# pi_3_hat_V3.net
KiCad netlist of a schematic drawn in EAGLE
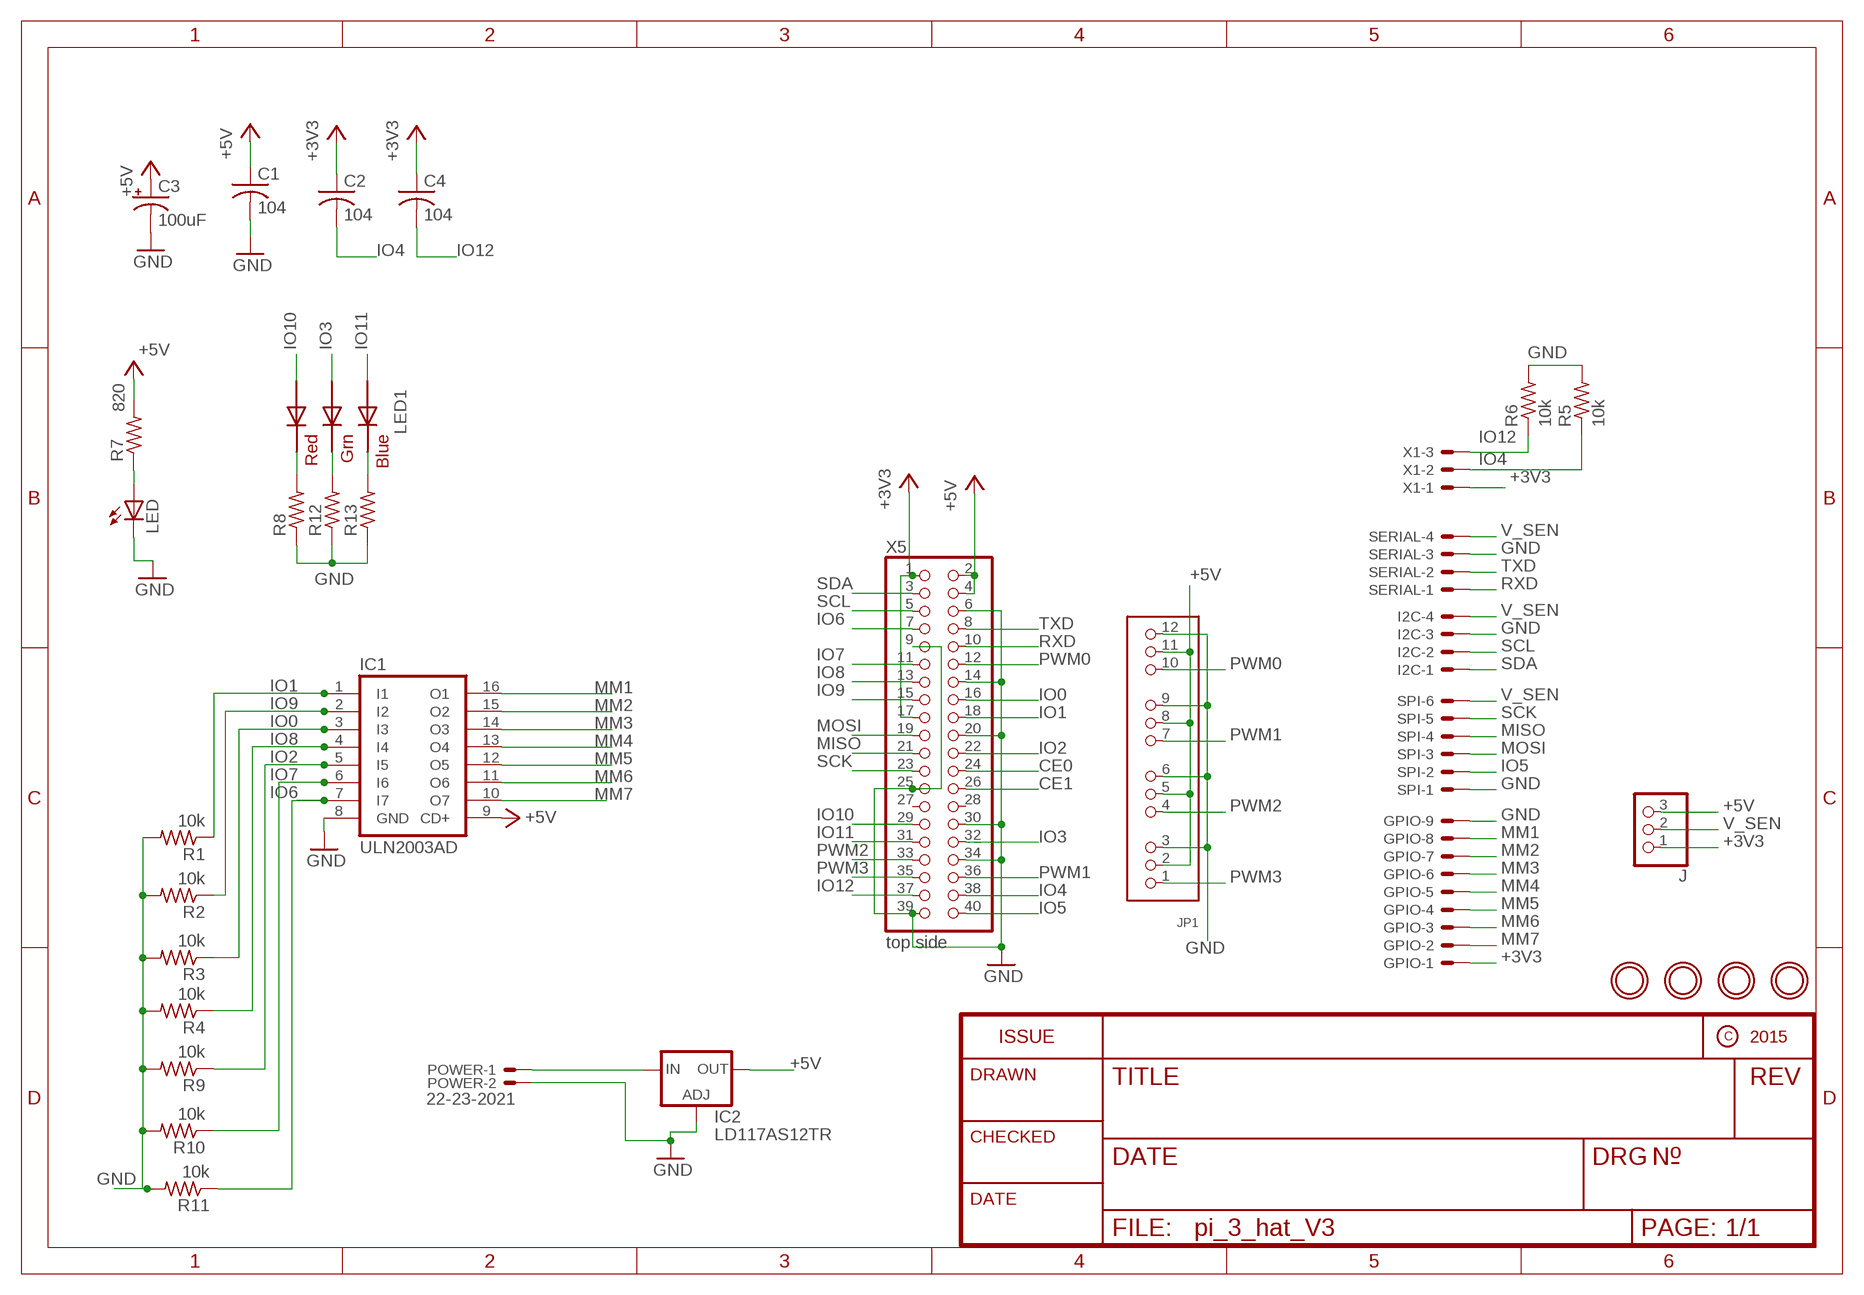
[diagram p0: schematic, sheet 1]

(export (version "E")
  (design (tool "Eeschema 10.0.6"))
  (components
    (comp (ref "C1")
      (value "104")
      (footprint "eagle-import:C1206")
      (libsource (lib "eagle-import") (part "C-USC1206"))
    )
    (comp (ref "C2")
      (value "104")
      (footprint "eagle-import:C1206")
      (libsource (lib "eagle-import") (part "C-USC1206"))
    )
    (comp (ref "C3")
      (value "100uF")
      (footprint "eagle-import:E2,5-6")
      (libsource (lib "eagle-import") (part "CPOL-USE2.5-6"))
    )
    (comp (ref "C4")
      (value "104")
      (footprint "eagle-import:C1206")
      (libsource (lib "eagle-import") (part "C-USC1206"))
    )
    (comp (ref "GPIO")
      (value "22-23-2091")
      (footprint "eagle-import:22-23-2091")
      (fields (field (name "MF") "MOLEX"))
      (libsource (lib "eagle-import") (part "22-23-2091"))
    )
    (comp (ref "I2C")
      (value "22-23-2041")
      (footprint "eagle-import:22-23-2041")
      (fields (field (name "MF") "MOLEX"))
      (libsource (lib "eagle-import") (part "22-23-2041"))
    )
    (comp (ref "IC1")
      (value "ULN2003AD")
      (footprint "eagle-import:SO16")
      (libsource (lib "eagle-import") (part "ULN2003AD"))
    )
    (comp (ref "IC2")
      (value "LD117AS12TR")
      (footprint "eagle-import:SOT223")
      (libsource (lib "eagle-import") (part "LD117A?S12TR"))
    )
    (comp (ref "J")
      (value "PINHD-1X3")
      (footprint "eagle-import:1X03")
      (libsource (lib "eagle-import") (part "PINHD-1X3"))
    )
    (comp (ref "JP1")
      (value "HEADER-3X04")
      (footprint "eagle-import:3X04")
      (libsource (lib "eagle-import") (part "HEADER-3X04"))
    )
    (comp (ref "LED")
      (value "LEDSMT1206")
      (footprint "eagle-import:1206")
      (libsource (lib "eagle-import") (part "LEDSMT1206"))
    )
    (comp (ref "LED1")
      (value "RGBLED5050")
      (footprint "eagle-import:RGBLED5050")
      (libsource (lib "eagle-import") (part "RGBLED5050"))
    )
    (comp (ref "POWER")
      (value "22-23-2021")
      (footprint "eagle-import:22-23-2021")
      (fields (field (name "MF") "MOLEX"))
      (libsource (lib "eagle-import") (part "22-23-2021"))
    )
    (comp (ref "R1")
      (value "10k")
      (footprint "eagle-import:R1206")
      (libsource (lib "eagle-import") (part "R-US_R1206"))
    )
    (comp (ref "R2")
      (value "10k")
      (footprint "eagle-import:R1206")
      (libsource (lib "eagle-import") (part "R-US_R1206"))
    )
    (comp (ref "R3")
      (value "10k")
      (footprint "eagle-import:R1206")
      (libsource (lib "eagle-import") (part "R-US_R1206"))
    )
    (comp (ref "R4")
      (value "10k")
      (footprint "eagle-import:R1206")
      (libsource (lib "eagle-import") (part "R-US_R1206"))
    )
    (comp (ref "R5")
      (value "10k")
      (footprint "eagle-import:R1206")
      (libsource (lib "eagle-import") (part "R-US_R1206"))
    )
    (comp (ref "R6")
      (value "10k")
      (footprint "eagle-import:R1206")
      (libsource (lib "eagle-import") (part "R-US_R1206"))
    )
    (comp (ref "R7")
      (value "820")
      (footprint "eagle-import:R1206")
      (libsource (lib "eagle-import") (part "R-US_R1206"))
    )
    (comp (ref "R8")
      (value "R-US_R1206")
      (footprint "eagle-import:R1206")
      (libsource (lib "eagle-import") (part "R-US_R1206"))
    )
    (comp (ref "R9")
      (value "10k")
      (footprint "eagle-import:R1206")
      (libsource (lib "eagle-import") (part "R-US_R1206"))
    )
    (comp (ref "R10")
      (value "10k")
      (footprint "eagle-import:R1206")
      (libsource (lib "eagle-import") (part "R-US_R1206"))
    )
    (comp (ref "R11")
      (value "10k")
      (footprint "eagle-import:R1206")
      (libsource (lib "eagle-import") (part "R-US_R1206"))
    )
    (comp (ref "R12")
      (value "R-US_R1206")
      (footprint "eagle-import:R1206")
      (libsource (lib "eagle-import") (part "R-US_R1206"))
    )
    (comp (ref "R13")
      (value "R-US_R1206")
      (footprint "eagle-import:R1206")
      (libsource (lib "eagle-import") (part "R-US_R1206"))
    )
    (comp (ref "SERIAL")
      (value "22-23-2041")
      (footprint "eagle-import:22-23-2041")
      (fields (field (name "MF") "MOLEX"))
      (libsource (lib "eagle-import") (part "22-23-2041"))
    )
    (comp (ref "SPI")
      (value "22-23-2061")
      (footprint "eagle-import:22-23-2061")
      (fields (field (name "MF") "MOLEX"))
      (libsource (lib "eagle-import") (part "22-23-2061"))
    )
    (comp (ref "U$4")
      (value "MOUNTINGHOLE2.5")
      (footprint "eagle-import:MOUNTINGHOLE_2.5_PLATED")
      (libsource (lib "eagle-import") (part "MOUNTINGHOLE2.5"))
    )
    (comp (ref "U$5")
      (value "MOUNTINGHOLE2.5")
      (footprint "eagle-import:MOUNTINGHOLE_2.5_PLATED")
      (libsource (lib "eagle-import") (part "MOUNTINGHOLE2.5"))
    )
    (comp (ref "U$6")
      (value "MOUNTINGHOLE2.5")
      (footprint "eagle-import:MOUNTINGHOLE_2.5_PLATED")
      (libsource (lib "eagle-import") (part "MOUNTINGHOLE2.5"))
    )
    (comp (ref "U$7")
      (value "MOUNTINGHOLE2.5")
      (footprint "eagle-import:MOUNTINGHOLE_2.5_PLATED")
      (libsource (lib "eagle-import") (part "MOUNTINGHOLE2.5"))
    )
    (comp (ref "X1")
      (value "22-23-2031")
      (footprint "eagle-import:22-23-2031")
      (fields (field (name "MF") "MOLEX"))
      (libsource (lib "eagle-import") (part "22-23-2031"))
    )
    (comp (ref "X5")
      (value "top side")
      (footprint "eagle-import:2X20")
      (libsource (lib "eagle-import") (part "PINHD-2X20"))
    )
  )
  (nets
    (net (code "1") (name "+3V3") (class "Default")
      (node (ref "C2") (pin "1") (pinfunction "1_1") (pintype "passive"))
      (node (ref "C4") (pin "1") (pinfunction "1_1") (pintype "passive"))
      (node (ref "GPIO") (pin "1") (pinfunction "S_1") (pintype "passive"))
      (node (ref "J") (pin "1") (pinfunction "1_1") (pintype "passive"))
      (node (ref "X1") (pin "1") (pinfunction "S_1") (pintype "passive"))
      (node (ref "X5") (pin "1") (pinfunction "1_1") (pintype "passive"))
      (node (ref "X5") (pin "17") (pinfunction "17_17") (pintype "passive"))
    )
    (net (code "2") (name "+5V") (class "Default")
      (node (ref "C1") (pin "1") (pinfunction "1_1") (pintype "passive"))
      (node (ref "C3") (pin "+") (pinfunction "+_+") (pintype "passive"))
      (node (ref "IC1") (pin "9") (pinfunction "CD+_9") (pintype "passive"))
      (node (ref "IC2") (pin "4") (pinfunction "OUT_4") (pintype "passive"))
      (node (ref "J") (pin "3") (pinfunction "3_3") (pintype "passive"))
      (node (ref "JP1") (pin "11") (pinfunction "11_11") (pintype "passive"))
      (node (ref "JP1") (pin "2") (pinfunction "2_2") (pintype "passive"))
      (node (ref "JP1") (pin "5") (pinfunction "5_5") (pintype "passive"))
      (node (ref "JP1") (pin "8") (pinfunction "8_8") (pintype "passive"))
      (node (ref "R7") (pin "2") (pinfunction "2_2") (pintype "passive"))
      (node (ref "X5") (pin "2") (pinfunction "2_2") (pintype "passive"))
      (node (ref "X5") (pin "4") (pinfunction "4_4") (pintype "passive"))
    )
    (net (code "3") (name "/CE0") (class "Default")
      (node (ref "X5") (pin "24") (pinfunction "24_24") (pintype "passive"))
    )
    (net (code "4") (name "/CE1") (class "Default")
      (node (ref "X5") (pin "26") (pinfunction "26_26") (pintype "passive"))
    )
    (net (code "5") (name "/IO0") (class "Default")
      (node (ref "IC1") (pin "3") (pinfunction "I3_3") (pintype "input"))
      (node (ref "R3") (pin "1") (pinfunction "1_1") (pintype "passive"))
      (node (ref "X5") (pin "16") (pinfunction "16_16") (pintype "passive"))
    )
    (net (code "6") (name "/IO1") (class "Default")
      (node (ref "IC1") (pin "1") (pinfunction "I1_1") (pintype "input"))
      (node (ref "R1") (pin "1") (pinfunction "1_1") (pintype "passive"))
      (node (ref "X5") (pin "18") (pinfunction "18_18") (pintype "passive"))
    )
    (net (code "7") (name "/IO2") (class "Default")
      (node (ref "IC1") (pin "5") (pinfunction "I5_5") (pintype "input"))
      (node (ref "R9") (pin "1") (pinfunction "1_1") (pintype "passive"))
      (node (ref "X5") (pin "22") (pinfunction "22_22") (pintype "passive"))
    )
    (net (code "8") (name "/IO3") (class "Default")
      (node (ref "LED1") (pin "1") (pinfunction "GREEN_A_1") (pintype "bidirectional"))
      (node (ref "X5") (pin "32") (pinfunction "32_32") (pintype "passive"))
    )
    (net (code "9") (name "/IO4") (class "Default")
      (node (ref "C2") (pin "2") (pinfunction "2_2") (pintype "passive"))
      (node (ref "R5") (pin "1") (pinfunction "1_1") (pintype "passive"))
      (node (ref "X1") (pin "2") (pinfunction "S_2") (pintype "passive"))
      (node (ref "X5") (pin "38") (pinfunction "38_38") (pintype "passive"))
    )
    (net (code "10") (name "/IO5") (class "Default")
      (node (ref "SPI") (pin "2") (pinfunction "S_2") (pintype "passive"))
      (node (ref "X5") (pin "40") (pinfunction "40_40") (pintype "passive"))
    )
    (net (code "11") (name "/IO6") (class "Default")
      (node (ref "IC1") (pin "7") (pinfunction "I7_7") (pintype "input"))
      (node (ref "R11") (pin "1") (pinfunction "1_1") (pintype "passive"))
      (node (ref "X5") (pin "7") (pinfunction "7_7") (pintype "passive"))
    )
    (net (code "12") (name "/IO7") (class "Default")
      (node (ref "IC1") (pin "6") (pinfunction "I6_6") (pintype "input"))
      (node (ref "R10") (pin "1") (pinfunction "1_1") (pintype "passive"))
      (node (ref "X5") (pin "11") (pinfunction "11_11") (pintype "passive"))
    )
    (net (code "13") (name "/IO8") (class "Default")
      (node (ref "IC1") (pin "4") (pinfunction "I4_4") (pintype "input"))
      (node (ref "R4") (pin "1") (pinfunction "1_1") (pintype "passive"))
      (node (ref "X5") (pin "13") (pinfunction "13_13") (pintype "passive"))
    )
    (net (code "14") (name "/IO9") (class "Default")
      (node (ref "IC1") (pin "2") (pinfunction "I2_2") (pintype "input"))
      (node (ref "R2") (pin "1") (pinfunction "1_1") (pintype "passive"))
      (node (ref "X5") (pin "15") (pinfunction "15_15") (pintype "passive"))
    )
    (net (code "15") (name "/IO10") (class "Default")
      (node (ref "LED1") (pin "2") (pinfunction "RED_A_2") (pintype "bidirectional"))
      (node (ref "X5") (pin "29") (pinfunction "29_29") (pintype "passive"))
    )
    (net (code "16") (name "/IO11") (class "Default")
      (node (ref "LED1") (pin "3") (pinfunction "BLUE_A_3") (pintype "bidirectional"))
      (node (ref "X5") (pin "31") (pinfunction "31_31") (pintype "passive"))
    )
    (net (code "17") (name "/IO12") (class "Default")
      (node (ref "C4") (pin "2") (pinfunction "2_2") (pintype "passive"))
      (node (ref "R6") (pin "1") (pinfunction "1_1") (pintype "passive"))
      (node (ref "X1") (pin "3") (pinfunction "S_3") (pintype "passive"))
      (node (ref "X5") (pin "37") (pinfunction "37_37") (pintype "passive"))
    )
    (net (code "18") (name "/MISO") (class "Default")
      (node (ref "SPI") (pin "4") (pinfunction "S_4") (pintype "passive"))
      (node (ref "X5") (pin "21") (pinfunction "21_21") (pintype "passive"))
    )
    (net (code "19") (name "/MM1") (class "Default")
      (node (ref "GPIO") (pin "8") (pinfunction "S_8") (pintype "passive"))
      (node (ref "IC1") (pin "16") (pinfunction "O1_16") (pintype "open_collector"))
    )
    (net (code "20") (name "/MM2") (class "Default")
      (node (ref "GPIO") (pin "7") (pinfunction "S_7") (pintype "passive"))
      (node (ref "IC1") (pin "15") (pinfunction "O2_15") (pintype "open_collector"))
    )
    (net (code "21") (name "/MM3") (class "Default")
      (node (ref "GPIO") (pin "6") (pinfunction "S_6") (pintype "passive"))
      (node (ref "IC1") (pin "14") (pinfunction "O3_14") (pintype "open_collector"))
    )
    (net (code "22") (name "/MM4") (class "Default")
      (node (ref "GPIO") (pin "5") (pinfunction "S_5") (pintype "passive"))
      (node (ref "IC1") (pin "13") (pinfunction "O4_13") (pintype "open_collector"))
    )
    (net (code "23") (name "/MM5") (class "Default")
      (node (ref "GPIO") (pin "4") (pinfunction "S_4") (pintype "passive"))
      (node (ref "IC1") (pin "12") (pinfunction "O5_12") (pintype "open_collector"))
    )
    (net (code "24") (name "/MM6") (class "Default")
      (node (ref "GPIO") (pin "3") (pinfunction "S_3") (pintype "passive"))
      (node (ref "IC1") (pin "11") (pinfunction "O6_11") (pintype "open_collector"))
    )
    (net (code "25") (name "/MM7") (class "Default")
      (node (ref "GPIO") (pin "2") (pinfunction "S_2") (pintype "passive"))
      (node (ref "IC1") (pin "10") (pinfunction "O7_10") (pintype "open_collector"))
    )
    (net (code "26") (name "/MOSI") (class "Default")
      (node (ref "SPI") (pin "3") (pinfunction "S_3") (pintype "passive"))
      (node (ref "X5") (pin "19") (pinfunction "19_19") (pintype "passive"))
    )
    (net (code "27") (name "/PWM0") (class "Default")
      (node (ref "JP1") (pin "10") (pinfunction "10_10") (pintype "passive"))
      (node (ref "X5") (pin "12") (pinfunction "12_12") (pintype "passive"))
    )
    (net (code "28") (name "/PWM1") (class "Default")
      (node (ref "JP1") (pin "7") (pinfunction "7_7") (pintype "passive"))
      (node (ref "X5") (pin "36") (pinfunction "36_36") (pintype "passive"))
    )
    (net (code "29") (name "/PWM2") (class "Default")
      (node (ref "JP1") (pin "4") (pinfunction "4_4") (pintype "passive"))
      (node (ref "X5") (pin "33") (pinfunction "33_33") (pintype "passive"))
    )
    (net (code "30") (name "/PWM3") (class "Default")
      (node (ref "JP1") (pin "1") (pinfunction "1_1") (pintype "passive"))
      (node (ref "X5") (pin "35") (pinfunction "35_35") (pintype "passive"))
    )
    (net (code "31") (name "/RXD") (class "Default")
      (node (ref "SERIAL") (pin "1") (pinfunction "S_1") (pintype "passive"))
      (node (ref "X5") (pin "10") (pinfunction "10_10") (pintype "passive"))
    )
    (net (code "32") (name "/SCK") (class "Default")
      (node (ref "SPI") (pin "5") (pinfunction "S_5") (pintype "passive"))
      (node (ref "X5") (pin "23") (pinfunction "23_23") (pintype "passive"))
    )
    (net (code "33") (name "/SCL") (class "Default")
      (node (ref "I2C") (pin "2") (pinfunction "S_2") (pintype "passive"))
      (node (ref "X5") (pin "5") (pinfunction "5_5") (pintype "passive"))
    )
    (net (code "34") (name "/SDA") (class "Default")
      (node (ref "I2C") (pin "1") (pinfunction "S_1") (pintype "passive"))
      (node (ref "X5") (pin "3") (pinfunction "3_3") (pintype "passive"))
    )
    (net (code "35") (name "/TXD") (class "Default")
      (node (ref "SERIAL") (pin "2") (pinfunction "S_2") (pintype "passive"))
      (node (ref "X5") (pin "8") (pinfunction "8_8") (pintype "passive"))
    )
    (net (code "36") (name "/V_SEN") (class "Default")
      (node (ref "I2C") (pin "4") (pinfunction "S_4") (pintype "passive"))
      (node (ref "J") (pin "2") (pinfunction "2_2") (pintype "passive"))
      (node (ref "SERIAL") (pin "4") (pinfunction "S_4") (pintype "passive"))
      (node (ref "SPI") (pin "6") (pinfunction "S_6") (pintype "passive"))
    )
    (net (code "37") (name "GND") (class "Default")
      (node (ref "C1") (pin "2") (pinfunction "2_2") (pintype "passive"))
      (node (ref "C3") (pin "-") (pinfunction "-_-") (pintype "passive"))
      (node (ref "GPIO") (pin "9") (pinfunction "S_9") (pintype "passive"))
      (node (ref "I2C") (pin "3") (pinfunction "S_3") (pintype "passive"))
      (node (ref "IC1") (pin "8") (pinfunction "GND_8") (pintype "power_in"))
      (node (ref "IC2") (pin "1") (pinfunction "ADJ_1") (pintype "input"))
      (node (ref "JP1") (pin "12") (pinfunction "12_12") (pintype "passive"))
      (node (ref "JP1") (pin "3") (pinfunction "3_3") (pintype "passive"))
      (node (ref "JP1") (pin "6") (pinfunction "6_6") (pintype "passive"))
      (node (ref "JP1") (pin "9") (pinfunction "9_9") (pintype "passive"))
      (node (ref "LED") (pin "C") (pinfunction "C_C") (pintype "passive"))
      (node (ref "POWER") (pin "2") (pinfunction "S_2") (pintype "passive"))
      (node (ref "R1") (pin "2") (pinfunction "2_2") (pintype "passive"))
      (node (ref "R10") (pin "2") (pinfunction "2_2") (pintype "passive"))
      (node (ref "R11") (pin "2") (pinfunction "2_2") (pintype "passive"))
      (node (ref "R12") (pin "1") (pinfunction "1_1") (pintype "passive"))
      (node (ref "R13") (pin "1") (pinfunction "1_1") (pintype "passive"))
      (node (ref "R2") (pin "2") (pinfunction "2_2") (pintype "passive"))
      (node (ref "R3") (pin "2") (pinfunction "2_2") (pintype "passive"))
      (node (ref "R4") (pin "2") (pinfunction "2_2") (pintype "passive"))
      (node (ref "R5") (pin "2") (pinfunction "2_2") (pintype "passive"))
      (node (ref "R6") (pin "2") (pinfunction "2_2") (pintype "passive"))
      (node (ref "R8") (pin "1") (pinfunction "1_1") (pintype "passive"))
      (node (ref "R9") (pin "2") (pinfunction "2_2") (pintype "passive"))
      (node (ref "SERIAL") (pin "3") (pinfunction "S_3") (pintype "passive"))
      (node (ref "SPI") (pin "1") (pinfunction "S_1") (pintype "passive"))
      (node (ref "X5") (pin "14") (pinfunction "14_14") (pintype "passive"))
      (node (ref "X5") (pin "20") (pinfunction "20_20") (pintype "passive"))
      (node (ref "X5") (pin "25") (pinfunction "25_25") (pintype "passive"))
      (node (ref "X5") (pin "30") (pinfunction "30_30") (pintype "passive"))
      (node (ref "X5") (pin "34") (pinfunction "34_34") (pintype "passive"))
      (node (ref "X5") (pin "39") (pinfunction "39_39") (pintype "passive"))
      (node (ref "X5") (pin "6") (pinfunction "6_6") (pintype "passive"))
      (node (ref "X5") (pin "9") (pinfunction "9_9") (pintype "passive"))
    )
    (net (code "38") (name "Net-(IC2-IN)") (class "Default")
      (node (ref "IC2") (pin "3") (pinfunction "IN_3") (pintype "input"))
      (node (ref "POWER") (pin "1") (pinfunction "S_1") (pintype "passive"))
    )
    (net (code "39") (name "Net-(LED-PadA)") (class "Default")
      (node (ref "LED") (pin "A") (pinfunction "A_A") (pintype "passive"))
      (node (ref "R7") (pin "1") (pinfunction "1_1") (pintype "passive"))
    )
    (net (code "40") (name "Net-(LED1-BLUE_C)") (class "Default")
      (node (ref "LED1") (pin "4") (pinfunction "BLUE_C_4") (pintype "bidirectional"))
      (node (ref "R13") (pin "2") (pinfunction "2_2") (pintype "passive"))
    )
    (net (code "41") (name "Net-(LED1-GREEN_C)") (class "Default")
      (node (ref "LED1") (pin "6") (pinfunction "GREEN_C_6") (pintype "bidirectional"))
      (node (ref "R12") (pin "2") (pinfunction "2_2") (pintype "passive"))
    )
    (net (code "42") (name "Net-(LED1-RED_C)") (class "Default")
      (node (ref "LED1") (pin "5") (pinfunction "RED_C_5") (pintype "bidirectional"))
      (node (ref "R8") (pin "2") (pinfunction "2_2") (pintype "passive"))
    )
    (net (code "43") (name "unconnected-(X5-Pad27)") (class "Default")
      (node (ref "X5") (pin "27") (pinfunction "27_27") (pintype "passive"))
    )
    (net (code "44") (name "unconnected-(X5-Pad28)") (class "Default")
      (node (ref "X5") (pin "28") (pinfunction "28_28") (pintype "passive"))
    )
  )
)
